# MCMainSch.net
KiCad netlist of a schematic drawn in Altium Designer
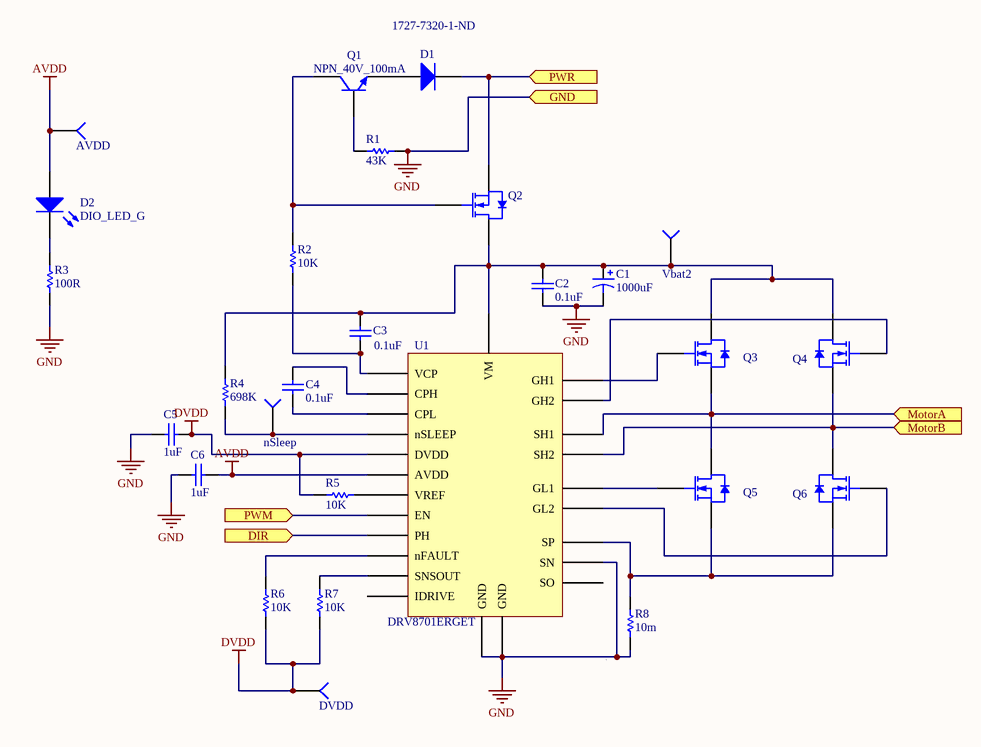
[diagram p0: MCMainSch.SchDoc]

(export (version "E")
  (design (tool "Eeschema 10.0.6"))
  (components
    (comp (ref "C1")
      (value "1000uF")
      (footprint "CAPR-2/4h6.8")
      (description "CAP ALUM 22UF 20% 50V RADIAL")
      (fields (field (name "MANUFACTURER") "Wurth Electronics Inc.") (field (name "MPN") "860020672011"))
      (libsource (lib "UWRT_Schematic_Library_2019") (part "CAP_22uF_POL"))
    )
    (comp (ref "C2")
      (value "0.1uF")
      (footprint "CAPC0603(1608)55_N")
      (description "CAP CER 0.1UF 16V X7R 0603")
      (fields (field (name "MPN") "CC0603KRX7R7BB104") (field (name "MANUFACTURER") "Yageo"))
      (libsource (lib "UWRT_Schematic_Library_2019") (part "CAP_0.1uF_16V_0603"))
    )
    (comp (ref "C3")
      (value "0.1uF")
      (footprint "CAPC0603(1608)55_N")
      (description "CAP CER 0.1UF 16V X7R 0603")
      (fields (field (name "MPN") "CC0603KRX7R7BB104") (field (name "MANUFACTURER") "Yageo"))
      (libsource (lib "UWRT_Schematic_Library_2019") (part "CAP_0.1uF_16V_0603"))
    )
    (comp (ref "C4")
      (value "0.1uF")
      (footprint "CAPC0603(1608)55_N")
      (description "CAP CER 0.1UF 16V X7R 0603")
      (fields (field (name "MPN") "CC0603KRX7R7BB104") (field (name "MANUFACTURER") "Yageo"))
      (libsource (lib "UWRT_Schematic_Library_2019") (part "CAP_0.1uF_16V_0603"))
    )
    (comp (ref "C5")
      (value "1uF")
      (footprint "CAPC0603(1608)55_N")
      (description "CAP CER 1UF 16V Y5V 0603")
      (fields (field (name "MPN") "CC0603ZRY5V7BB105") (field (name "MANUFACTURER") "Yageo"))
      (libsource (lib "UWRT_Schematic_Library_2019") (part "CAP_1uF_16V_0603"))
    )
    (comp (ref "C6")
      (value "1uF")
      (footprint "CAPC0603(1608)55_N")
      (description "CAP CER 1UF 16V Y5V 0603")
      (fields (field (name "MPN") "CC0603ZRY5V7BB105") (field (name "MANUFACTURER") "Yageo"))
      (libsource (lib "UWRT_Schematic_Library_2019") (part "CAP_1uF_16V_0603"))
    )
    (comp (ref "D1")
      (value "0")
      (footprint "DIODSOD-123")
      (description "ESD PROTECTION DIODE")
      (fields
        (field (name "MPN") "BAS16GW")
        (field (name "MANUFACTURER") "Nexperia")
        (field (name "SUPPLIER PART NUMBER 1") "1727-7320-1-ND")
      )
      (libsource (lib "UWRT_Schematic_Library_2019") (part "DIO_BAS16GW"))
    )
    (comp (ref "D2")
      (value "DIO_LED_G")
      (footprint "LED_0805_LINE")
      (description "LED GREEN DIFFUSED 0805 SMD")
      (fields (field (name "MPN") "LG R971-KN-1") (field (name "MANUFACTURER") "OSRAM"))
      (libsource (lib "UWRT_Schematic_Library_2019") (part "DIO_LED_G"))
    )
    (comp (ref "Q1")
      (value "NPN_40V_100mA")
      (footprint "SOT23-3")
      (description "TRANS NPN 40V 0.2A SOT23")
      (fields (field (name "MANUFACTURER") "Micro Commercial Co") (field (name "MPN") "MMBT3904-TP"))
      (libsource (lib "UWRT_Schematic_Library_2019") (part "NPN_40V_100mA"))
    )
    (comp (ref "Q2")
      (value "NMOS_40V_75A")
      (footprint "SOT404")
      (description "MOSFET N-CH 40V 75A D2PAK")
      (fields (field (name "MPN") "BUK768R1-40E,118") (field (name "MANUFACTURER") "Nexperia USA Inc."))
      (libsource (lib "UWRT_Schematic_Library_2019") (part "NMOS_40V_75A"))
    )
    (comp (ref "Q3")
      (value "NMOS_40V_75A")
      (footprint "SOT404")
      (description "MOSFET N-CH 40V 75A D2PAK")
      (fields (field (name "MPN") "BUK768R1-40E,118") (field (name "MANUFACTURER") "Nexperia USA Inc."))
      (libsource (lib "UWRT_Schematic_Library_2019") (part "NMOS_40V_75A"))
    )
    (comp (ref "Q4")
      (value "NMOS_40V_75A")
      (footprint "SOT404")
      (description "MOSFET N-CH 40V 75A D2PAK")
      (fields (field (name "MPN") "BUK768R1-40E,118") (field (name "MANUFACTURER") "Nexperia USA Inc."))
      (libsource (lib "UWRT_Schematic_Library_2019") (part "NMOS_40V_75A"))
    )
    (comp (ref "Q5")
      (value "NMOS_40V_75A")
      (footprint "SOT404")
      (description "MOSFET N-CH 40V 75A D2PAK")
      (fields (field (name "MPN") "BUK768R1-40E,118") (field (name "MANUFACTURER") "Nexperia USA Inc."))
      (libsource (lib "UWRT_Schematic_Library_2019") (part "NMOS_40V_75A"))
    )
    (comp (ref "Q6")
      (value "NMOS_40V_75A")
      (footprint "SOT404")
      (description "MOSFET N-CH 40V 75A D2PAK")
      (fields (field (name "MPN") "BUK768R1-40E,118") (field (name "MANUFACTURER") "Nexperia USA Inc."))
      (libsource (lib "UWRT_Schematic_Library_2019") (part "NMOS_40V_75A"))
    )
    (comp (ref "R1")
      (value "43K")
      (footprint "RESC0603(1608)_N")
      (description "RES SMD 43K OHM 5% 1/10W 0603")
      (fields (field (name "MANUFACTURER") "Yageo") (field (name "MPN") "RC0603JR-0743KL"))
      (libsource (lib "UWRT_Schematic_Library_2019") (part "RES_43K_0603"))
    )
    (comp (ref "R2")
      (value "10K")
      (footprint "RESC0603(1608)_N")
      (description "RES SMD 10K OHM 5% 1/10W 0603")
      (fields (field (name "MANUFACTURER") "Yageo") (field (name "MPN") "RC0603JR-0710KL"))
      (libsource (lib "UWRT_Schematic_Library_2019") (part "RES_10K_0603"))
    )
    (comp (ref "R3")
      (value "100R")
      (footprint "RESC0603(1608)_N")
      (description "RES SMD 0 OHM JUMPER 1/10W 0603")
      (fields (field (name "MANUFACTURER") "Yageo") (field (name "MPN") "RC0603JR-070RL"))
      (libsource (lib "UWRT_Schematic_Library_2019") (part "RES_0R_0603"))
    )
    (comp (ref "R4")
      (value "698K")
      (footprint "RESC0603(1608)_N")
      (description "RES SMD 698K OHM 1% 1/10W 0603")
      (fields (field (name "MANUFACTURER") "Yageo") (field (name "MPN") "RC0603FR-07698KL"))
      (libsource (lib "UWRT_Schematic_Library_2019") (part "RES_698K_0603"))
    )
    (comp (ref "R5")
      (value "10K")
      (footprint "RESC0603(1608)_N")
      (description "RES SMD 10K OHM 5% 1/10W 0603")
      (fields (field (name "MANUFACTURER") "Yageo") (field (name "MPN") "RC0603JR-0710KL"))
      (libsource (lib "UWRT_Schematic_Library_2019") (part "RES_10K_0603"))
    )
    (comp (ref "R6")
      (value "10K")
      (footprint "RESC0603(1608)_N")
      (description "RES SMD 10K OHM 5% 1/10W 0603")
      (fields (field (name "MANUFACTURER") "Yageo") (field (name "MPN") "RC0603JR-0710KL"))
      (libsource (lib "UWRT_Schematic_Library_2019") (part "RES_10K_0603"))
    )
    (comp (ref "R7")
      (value "10K")
      (footprint "RESC0603(1608)_N")
      (description "RES SMD 10K OHM 5% 1/10W 0603")
      (fields (field (name "MANUFACTURER") "Yageo") (field (name "MPN") "RC0603JR-0710KL"))
      (libsource (lib "UWRT_Schematic_Library_2019") (part "RES_10K_0603"))
    )
    (comp (ref "R8")
      (value "10m")
      (footprint "STAC-CSS2725-099H_V")
      (description "RES SMD 10mOHM 1% 4W 2728")
      (fields (field (name "MANUFACTURER") "Yageo") (field (name "MPN") "RC0603FR-07698KL"))
      (libsource (lib "UWRT_Schematic_Library_2019") (part "RES_10m_2728"))
    )
    (comp (ref "TP1")
      (value "AVDD")
      (footprint "TESTPOINT")
      (description "TESTPOINT_SMD")
      (libsource (lib "UWRT_Schematic_Library_2019") (part "*"))
    )
    (comp (ref "TP2")
      (value "Vbat2")
      (footprint "TESTPOINT")
      (description "TESTPOINT_SMD")
      (libsource (lib "UWRT_Schematic_Library_2019") (part "*"))
    )
    (comp (ref "TP3")
      (value "nSleep")
      (footprint "TESTPOINT")
      (description "TESTPOINT_SMD")
      (libsource (lib "UWRT_Schematic_Library_2019") (part "*"))
    )
    (comp (ref "TP4")
      (value "DVDD")
      (footprint "TESTPOINT")
      (description "TESTPOINT_SMD")
      (libsource (lib "UWRT_Schematic_Library_2019") (part "*"))
    )
    (comp (ref "U1")
      (value "DRV8701ERGET")
      (footprint "VFQFPN-24_N")
      (fields (field (name "MANUFACTURER") "Texas Instruments"))
      (libsource (lib "MCSchLib") (part "IC Motor Driver"))
    )
  )
  (nets
    (net (code "1") (name "/DIR") (class "Default")
      (node (ref "U1") (pin "9") (pinfunction "PH_9") (pintype "passive"))
    )
    (net (code "2") (name "/MotorA") (class "Default")
      (node (ref "Q3") (pin "3") (pinfunction "S_3") (pintype "passive"))
      (node (ref "Q5") (pin "4") (pinfunction "D_4") (pintype "passive"))
      (node (ref "U1") (pin "17") (pinfunction "SH1_17") (pintype "passive"))
    )
    (net (code "3") (name "/MotorB") (class "Default")
      (node (ref "Q4") (pin "3") (pinfunction "S_3") (pintype "passive"))
      (node (ref "Q6") (pin "4") (pinfunction "D_4") (pintype "passive"))
      (node (ref "U1") (pin "18") (pinfunction "SH2_18") (pintype "passive"))
    )
    (net (code "4") (name "/PWM") (class "Default")
      (node (ref "U1") (pin "8") (pinfunction "EN_8") (pintype "passive"))
    )
    (net (code "5") (name "/PWR") (class "Default")
      (node (ref "D1") (pin "2") (pinfunction "K_2") (pintype "passive"))
      (node (ref "Q2") (pin "3") (pinfunction "S_3") (pintype "passive"))
    )
    (net (code "6") (name "AVDD") (class "Default")
      (node (ref "C6") (pin "2") (pinfunction "2_2") (pintype "passive"))
      (node (ref "D2") (pin "1") (pinfunction "A_1") (pintype "passive"))
      (node (ref "TP1") (pin "1") (pinfunction "=value_1") (pintype "passive"))
      (node (ref "U1") (pin "6") (pinfunction "AVDD_6") (pintype "passive"))
    )
    (net (code "7") (name "DVDD") (class "Default")
      (node (ref "C5") (pin "2") (pinfunction "2_2") (pintype "passive"))
      (node (ref "R5") (pin "1") (pinfunction "1_1") (pintype "passive"))
      (node (ref "R6") (pin "1") (pinfunction "1_1") (pintype "passive"))
      (node (ref "R7") (pin "1") (pinfunction "1_1") (pintype "passive"))
      (node (ref "TP4") (pin "1") (pinfunction "=value_1") (pintype "passive"))
      (node (ref "U1") (pin "5") (pinfunction "DVDD_5") (pintype "passive"))
    )
    (net (code "8") (name "GND") (class "Default")
      (node (ref "C1") (pin "2") (pinfunction "2_2") (pintype "passive"))
      (node (ref "C2") (pin "1") (pinfunction "1_1") (pintype "passive"))
      (node (ref "C5") (pin "1") (pinfunction "1_1") (pintype "passive"))
      (node (ref "C6") (pin "1") (pinfunction "1_1") (pintype "passive"))
      (node (ref "R1") (pin "1") (pinfunction "1_1") (pintype "passive"))
      (node (ref "R3") (pin "1") (pinfunction "1_1") (pintype "passive"))
      (node (ref "R8") (pin "1") (pinfunction "1_1") (pintype "passive"))
      (node (ref "U1") (pin "13") (pinfunction "GND_13") (pintype "passive"))
      (node (ref "U1") (pin "14") (pinfunction "GND_14") (pintype "passive"))
      (node (ref "U1") (pin "22") (pinfunction "SN_22") (pintype "passive"))
    )
    (net (code "9") (name "Net-(D1-A)") (class "Default")
      (node (ref "D1") (pin "1") (pinfunction "A_1") (pintype "passive"))
      (node (ref "Q1") (pin "2") (pinfunction "E_2") (pintype "passive"))
    )
    (net (code "10") (name "Net-(D2-K)") (class "Default")
      (node (ref "D2") (pin "2") (pinfunction "K_2") (pintype "passive"))
      (node (ref "R3") (pin "2") (pinfunction "2_2") (pintype "passive"))
    )
    (net (code "11") (name "Net-(Q1-B)") (class "Default")
      (node (ref "Q1") (pin "1") (pinfunction "B_1") (pintype "passive"))
      (node (ref "R1") (pin "2") (pinfunction "2_2") (pintype "passive"))
    )
    (net (code "12") (name "Net-(Q1-C)") (class "Default")
      (node (ref "Q1") (pin "3") (pinfunction "C_3") (pintype "passive"))
      (node (ref "Q2") (pin "1") (pinfunction "G_1") (pintype "passive"))
      (node (ref "R2") (pin "2") (pinfunction "2_2") (pintype "passive"))
    )
    (net (code "13") (name "Net-(Q2-D)") (class "Default")
      (node (ref "C1") (pin "1") (pinfunction "1_1") (pintype "passive"))
      (node (ref "C2") (pin "2") (pinfunction "2_2") (pintype "passive"))
      (node (ref "C3") (pin "2") (pinfunction "2_2") (pintype "passive"))
      (node (ref "Q2") (pin "4") (pinfunction "D_4") (pintype "passive"))
      (node (ref "Q3") (pin "4") (pinfunction "D_4") (pintype "passive"))
      (node (ref "Q4") (pin "4") (pinfunction "D_4") (pintype "passive"))
      (node (ref "R4") (pin "2") (pinfunction "2_2") (pintype "passive"))
      (node (ref "TP2") (pin "1") (pinfunction "=value_1") (pintype "passive"))
      (node (ref "U1") (pin "24") (pinfunction "VM_24") (pintype "passive"))
    )
    (net (code "14") (name "Net-(Q3-G)") (class "Default")
      (node (ref "Q3") (pin "1") (pinfunction "G_1") (pintype "passive"))
      (node (ref "U1") (pin "15") (pinfunction "GH1_15") (pintype "passive"))
    )
    (net (code "15") (name "Net-(Q4-G)") (class "Default")
      (node (ref "Q4") (pin "1") (pinfunction "G_1") (pintype "passive"))
      (node (ref "U1") (pin "16") (pinfunction "GH2_16") (pintype "passive"))
    )
    (net (code "16") (name "Net-(Q5-G)") (class "Default")
      (node (ref "Q5") (pin "1") (pinfunction "G_1") (pintype "passive"))
      (node (ref "U1") (pin "19") (pinfunction "GL1_19") (pintype "passive"))
    )
    (net (code "17") (name "Net-(Q5-S)") (class "Default")
      (node (ref "Q5") (pin "3") (pinfunction "S_3") (pintype "passive"))
      (node (ref "Q6") (pin "3") (pinfunction "S_3") (pintype "passive"))
      (node (ref "R8") (pin "2") (pinfunction "2_2") (pintype "passive"))
      (node (ref "U1") (pin "21") (pinfunction "SP_21") (pintype "passive"))
    )
    (net (code "18") (name "Net-(Q6-G)") (class "Default")
      (node (ref "Q6") (pin "1") (pinfunction "G_1") (pintype "passive"))
      (node (ref "U1") (pin "20") (pinfunction "GL2_20") (pintype "passive"))
    )
    (net (code "19") (name "Net-(TP3-=value)") (class "Default")
      (node (ref "R4") (pin "1") (pinfunction "1_1") (pintype "passive"))
      (node (ref "TP3") (pin "1") (pinfunction "=value_1") (pintype "passive"))
      (node (ref "U1") (pin "4") (pinfunction "nSLEEP_4") (pintype "passive"))
    )
    (net (code "20") (name "Net-(U1-CPH)") (class "Default")
      (node (ref "C4") (pin "2") (pinfunction "2_2") (pintype "passive"))
      (node (ref "U1") (pin "2") (pinfunction "CPH_2") (pintype "passive"))
    )
    (net (code "21") (name "Net-(U1-CPL)") (class "Default")
      (node (ref "C4") (pin "1") (pinfunction "1_1") (pintype "passive"))
      (node (ref "U1") (pin "3") (pinfunction "CPL_3") (pintype "passive"))
    )
    (net (code "22") (name "Net-(U1-SNSOUT)") (class "Default")
      (node (ref "R7") (pin "2") (pinfunction "2_2") (pintype "passive"))
      (node (ref "U1") (pin "11") (pinfunction "SNSOUT_11") (pintype "passive"))
    )
    (net (code "23") (name "Net-(U1-VCP)") (class "Default")
      (node (ref "C3") (pin "1") (pinfunction "1_1") (pintype "passive"))
      (node (ref "R2") (pin "1") (pinfunction "1_1") (pintype "passive"))
      (node (ref "U1") (pin "1") (pinfunction "VCP_1") (pintype "passive"))
    )
    (net (code "24") (name "Net-(U1-VREF)") (class "Default")
      (node (ref "R5") (pin "2") (pinfunction "2_2") (pintype "passive"))
      (node (ref "U1") (pin "7") (pinfunction "VREF_7") (pintype "passive"))
    )
    (net (code "25") (name "Net-(U1-nFAULT)") (class "Default")
      (node (ref "R6") (pin "2") (pinfunction "2_2") (pintype "passive"))
      (node (ref "U1") (pin "10") (pinfunction "nFAULT_10") (pintype "passive"))
    )
    (net (code "26") (name "unconnected-(U1-GND-Pad25)") (class "Default")
      (node (ref "U1") (pin "25") (pinfunction "GND_25") (pintype "passive"))
    )
    (net (code "27") (name "unconnected-(U1-IDRIVE-Pad12)") (class "Default")
      (node (ref "U1") (pin "12") (pinfunction "IDRIVE_12") (pintype "passive"))
    )
    (net (code "28") (name "unconnected-(U1-SO-Pad23)") (class "Default")
      (node (ref "U1") (pin "23") (pinfunction "SO_23") (pintype "passive"))
    )
  )
)
